# Analog.net
KiCad netlist of a schematic drawn in Altium Designer
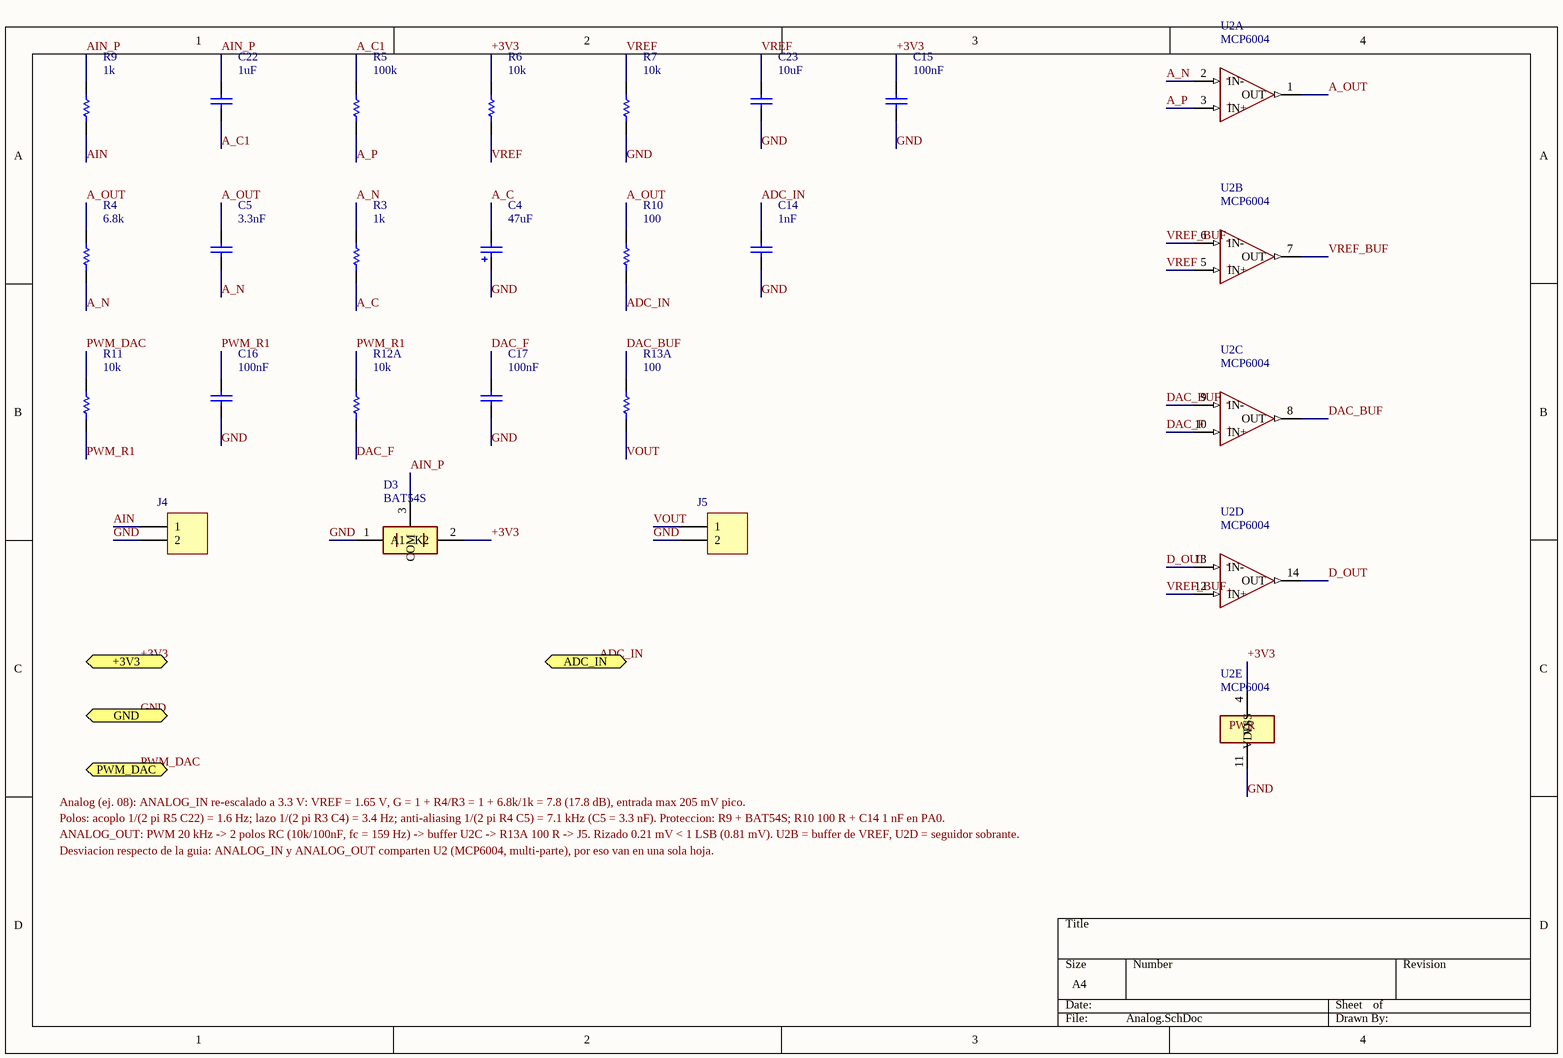
[diagram p0: Analog.SchDoc]

(export (version "E")
  (design (tool "Eeschema 10.0.6"))
  (components
    (comp (ref "C4")
      (value "47uF")
      (description "Electrolitico 47 uF 16 V (polo del lazo 3.4 Hz)")
      (fields
        (field (name "MANUFACTURER") "Panasonic")
        (field (name "MANUFACTURER PART NUMBER") "EEU-FR1C470")
        (field (name "PUBLISHER") "Altium Limited")
      )
      (libsource (lib "Miscellaneous Devices") (part "Cap Pol1"))
    )
    (comp (ref "C5")
      (value "3.3nF")
      (description "Capacitor 3.3nF")
      (fields
        (field (name "MANUFACTURER") "KEMET")
        (field (name "MANUFACTURER PART NUMBER") "C0603C3323.3nF")
        (field (name "PUBLISHER") "Altium Limited")
      )
      (libsource (lib "Miscellaneous Devices") (part "Cap"))
    )
    (comp (ref "C14")
      (value "1nF")
      (description "Capacitor 1nF")
      (fields
        (field (name "MANUFACTURER") "KEMET")
        (field (name "MANUFACTURER PART NUMBER") "C0603C1021nF")
        (field (name "PUBLISHER") "Altium Limited")
      )
      (libsource (lib "Miscellaneous Devices") (part "Cap"))
    )
    (comp (ref "C15")
      (value "100nF")
      (description "Capacitor 100nF")
      (fields
        (field (name "MANUFACTURER") "KEMET")
        (field (name "MANUFACTURER PART NUMBER") "C0603C100nF")
        (field (name "PUBLISHER") "Altium Limited")
      )
      (libsource (lib "Miscellaneous Devices") (part "Cap"))
    )
    (comp (ref "C16")
      (value "100nF")
      (description "Capacitor 100nF")
      (fields
        (field (name "MANUFACTURER") "KEMET")
        (field (name "MANUFACTURER PART NUMBER") "C0603C100nF")
        (field (name "PUBLISHER") "Altium Limited")
      )
      (libsource (lib "Miscellaneous Devices") (part "Cap"))
    )
    (comp (ref "C17")
      (value "100nF")
      (description "Capacitor 100nF")
      (fields
        (field (name "MANUFACTURER") "KEMET")
        (field (name "MANUFACTURER PART NUMBER") "C0603C100nF")
        (field (name "PUBLISHER") "Altium Limited")
      )
      (libsource (lib "Miscellaneous Devices") (part "Cap"))
    )
    (comp (ref "C22")
      (value "1uF")
      (description "Capacitor 1uF")
      (fields
        (field (name "MANUFACTURER") "KEMET")
        (field (name "MANUFACTURER PART NUMBER") "C0603C1051uF")
        (field (name "PUBLISHER") "Altium Limited")
      )
      (libsource (lib "Miscellaneous Devices") (part "Cap"))
    )
    (comp (ref "C23")
      (value "10uF")
      (description "Capacitor 10uF")
      (fields
        (field (name "MANUFACTURER") "KEMET")
        (field (name "MANUFACTURER PART NUMBER") "C0805C10610uF")
        (field (name "PUBLISHER") "Altium Limited")
      )
      (libsource (lib "Miscellaneous Devices") (part "Cap"))
    )
    (comp (ref "D3")
      (value "BAT54S")
      (footprint "SOT-23_N")
      (description "Dual Schottky series pair SOT-23 (clamp)")
      (fields (field (name "MANUFACTURER") "Nexperia"))
      (libsource (lib "*") (part "BAT54S"))
    )
    (comp (ref "J4")
      (value "Header 2")
      (description "Entrada analogica +-200 mV: pin1 senal, pin2 GND")
      (fields
        (field (name "MANUFACTURER") "Generic")
        (field (name "MANUFACTURER PART NUMBER") "Pin header 1x2")
        (field (name "PUBLISHER") "Altium Limited")
      )
      (libsource (lib "Miscellaneous Connectors") (part "Header 2"))
    )
    (comp (ref "J5")
      (value "Header 2")
      (description "Salida analogica 0-3.3 V: pin1 VOUT, pin2 GND")
      (fields
        (field (name "MANUFACTURER") "Generic")
        (field (name "MANUFACTURER PART NUMBER") "Pin header 1x2")
        (field (name "PUBLISHER") "Altium Limited")
      )
      (libsource (lib "Miscellaneous Connectors") (part "Header 2"))
    )
    (comp (ref "R3")
      (value "1k")
      (description "Resistor 1k 0603")
      (fields
        (field (name "MANUFACTURER") "Yageo")
        (field (name "MANUFACTURER PART NUMBER") "RC0603FR-071K")
        (field (name "PUBLISHER") "Altium Limited")
      )
      (libsource (lib "Miscellaneous Devices") (part "Res1"))
    )
    (comp (ref "R4")
      (value "6.8k")
      (description "Resistor 6.8k 0603")
      (fields
        (field (name "MANUFACTURER") "Yageo")
        (field (name "MANUFACTURER PART NUMBER") "RC0603FR-076.8K")
        (field (name "PUBLISHER") "Altium Limited")
      )
      (libsource (lib "Miscellaneous Devices") (part "Res1"))
    )
    (comp (ref "R5")
      (value "100k")
      (description "Resistor 100k 0603")
      (fields
        (field (name "MANUFACTURER") "Yageo")
        (field (name "MANUFACTURER PART NUMBER") "RC0603FR-07100K")
        (field (name "PUBLISHER") "Altium Limited")
      )
      (libsource (lib "Miscellaneous Devices") (part "Res1"))
    )
    (comp (ref "R6")
      (value "10k")
      (description "Resistor 10k 0603")
      (fields
        (field (name "MANUFACTURER") "Yageo")
        (field (name "MANUFACTURER PART NUMBER") "RC0603FR-0710K")
        (field (name "PUBLISHER") "Altium Limited")
      )
      (libsource (lib "Miscellaneous Devices") (part "Res1"))
    )
    (comp (ref "R7")
      (value "10k")
      (description "Resistor 10k 0603")
      (fields
        (field (name "MANUFACTURER") "Yageo")
        (field (name "MANUFACTURER PART NUMBER") "RC0603FR-0710K")
        (field (name "PUBLISHER") "Altium Limited")
      )
      (libsource (lib "Miscellaneous Devices") (part "Res1"))
    )
    (comp (ref "R9")
      (value "1k")
      (description "Resistor 1k 0603")
      (fields
        (field (name "MANUFACTURER") "Yageo")
        (field (name "MANUFACTURER PART NUMBER") "RC0603FR-071K")
        (field (name "PUBLISHER") "Altium Limited")
      )
      (libsource (lib "Miscellaneous Devices") (part "Res1"))
    )
    (comp (ref "R10")
      (value "100")
      (description "Resistor 100 0603")
      (fields
        (field (name "MANUFACTURER") "Yageo")
        (field (name "MANUFACTURER PART NUMBER") "RC0603FR-07100")
        (field (name "PUBLISHER") "Altium Limited")
      )
      (libsource (lib "Miscellaneous Devices") (part "Res1"))
    )
    (comp (ref "R11")
      (value "10k")
      (description "Resistor 10k 0603")
      (fields
        (field (name "MANUFACTURER") "Yageo")
        (field (name "MANUFACTURER PART NUMBER") "RC0603FR-0710K")
        (field (name "PUBLISHER") "Altium Limited")
      )
      (libsource (lib "Miscellaneous Devices") (part "Res1"))
    )
    (comp (ref "R12A")
      (value "10k")
      (description "Resistor 10k 0603")
      (fields
        (field (name "MANUFACTURER") "Yageo")
        (field (name "MANUFACTURER PART NUMBER") "RC0603FR-0710K")
        (field (name "PUBLISHER") "Altium Limited")
      )
      (libsource (lib "Miscellaneous Devices") (part "Res1"))
    )
    (comp (ref "R13A")
      (value "100")
      (description "Resistor 100 0603")
      (fields
        (field (name "MANUFACTURER") "Yageo")
        (field (name "MANUFACTURER PART NUMBER") "RC0603FR-07100")
        (field (name "PUBLISHER") "Altium Limited")
      )
      (libsource (lib "Miscellaneous Devices") (part "Res1"))
    )
    (comp (ref "U2")
      (value "MCP6004")
      (footprint "DIP-14")
      (description "MCP6004 quad op-amp rail-to-rail 1 MHz (A-D) + power part E, PDIP-14")
      (fields
        (field (name "MANUFACTURER") "Microchip")
        (field (name "MANUFACTURER PART NUMBER") "MCP6004-I/P")
      )
      (libsource (lib "*") (part "MCP6004"))
    )
  )
  (nets
    (net (code "1") (name "/+3V3") (class "Default")
      (node (ref "C15") (pin "2") (pinfunction "2_2") (pintype "passive"))
      (node (ref "D3") (pin "2") (pinfunction "K2_2") (pintype "passive"))
      (node (ref "R6") (pin "2") (pinfunction "2_2") (pintype "passive"))
      (node (ref "U2") (pin "4") (pinfunction "VDD_4") (pintype "power_in"))
    )
    (net (code "2") (name "/ADC_IN") (class "Default")
      (node (ref "C14") (pin "2") (pinfunction "2_2") (pintype "passive"))
      (node (ref "R10") (pin "1") (pinfunction "1_1") (pintype "passive"))
    )
    (net (code "3") (name "/AIN") (class "Default")
      (node (ref "J4") (pin "1") (pinfunction "1_1") (pintype "passive"))
      (node (ref "R9") (pin "1") (pinfunction "1_1") (pintype "passive"))
    )
    (net (code "4") (name "/AIN_P") (class "Default")
      (node (ref "C22") (pin "2") (pinfunction "2_2") (pintype "passive"))
      (node (ref "D3") (pin "3") (pinfunction "COM_3") (pintype "passive"))
      (node (ref "R9") (pin "2") (pinfunction "2_2") (pintype "passive"))
    )
    (net (code "5") (name "/A_C") (class "Default")
      (node (ref "C4") (pin "2") (pinfunction "2_2") (pintype "passive"))
      (node (ref "R3") (pin "1") (pinfunction "1_1") (pintype "passive"))
    )
    (net (code "6") (name "/A_C1") (class "Default")
      (node (ref "C22") (pin "1") (pinfunction "1_1") (pintype "passive"))
      (node (ref "R5") (pin "2") (pinfunction "2_2") (pintype "passive"))
    )
    (net (code "7") (name "/A_N") (class "Default")
      (node (ref "C5") (pin "1") (pinfunction "1_1") (pintype "passive"))
      (node (ref "R3") (pin "2") (pinfunction "2_2") (pintype "passive"))
      (node (ref "R4") (pin "1") (pinfunction "1_1") (pintype "passive"))
      (node (ref "U2") (pin "2") (pinfunction "IN-_2") (pintype "input"))
    )
    (net (code "8") (name "/A_OUT") (class "Default")
      (node (ref "C5") (pin "2") (pinfunction "2_2") (pintype "passive"))
      (node (ref "R10") (pin "2") (pinfunction "2_2") (pintype "passive"))
      (node (ref "R4") (pin "2") (pinfunction "2_2") (pintype "passive"))
      (node (ref "U2") (pin "1") (pinfunction "OUT_1") (pintype "output"))
    )
    (net (code "9") (name "/A_P") (class "Default")
      (node (ref "R5") (pin "1") (pinfunction "1_1") (pintype "passive"))
      (node (ref "U2") (pin "3") (pinfunction "IN+_3") (pintype "input"))
    )
    (net (code "10") (name "/DAC_BUF") (class "Default")
      (node (ref "R13A") (pin "2") (pinfunction "2_2") (pintype "passive"))
      (node (ref "U2") (pin "8") (pinfunction "OUT_8") (pintype "output"))
      (node (ref "U2") (pin "9") (pinfunction "IN-_9") (pintype "input"))
    )
    (net (code "11") (name "/DAC_F") (class "Default")
      (node (ref "C17") (pin "2") (pinfunction "2_2") (pintype "passive"))
      (node (ref "R12A") (pin "1") (pinfunction "1_1") (pintype "passive"))
      (node (ref "U2") (pin "10") (pinfunction "IN+_10") (pintype "input"))
    )
    (net (code "12") (name "/D_OUT") (class "Default")
      (node (ref "U2") (pin "13") (pinfunction "IN-_13") (pintype "input"))
      (node (ref "U2") (pin "14") (pinfunction "OUT_14") (pintype "output"))
    )
    (net (code "13") (name "/GND") (class "Default")
      (node (ref "C14") (pin "1") (pinfunction "1_1") (pintype "passive"))
      (node (ref "C15") (pin "1") (pinfunction "1_1") (pintype "passive"))
      (node (ref "C16") (pin "1") (pinfunction "1_1") (pintype "passive"))
      (node (ref "C17") (pin "1") (pinfunction "1_1") (pintype "passive"))
      (node (ref "C23") (pin "1") (pinfunction "1_1") (pintype "passive"))
      (node (ref "C4") (pin "1") (pinfunction "1_1") (pintype "passive"))
      (node (ref "D3") (pin "1") (pinfunction "A1_1") (pintype "passive"))
      (node (ref "J4") (pin "2") (pinfunction "2_2") (pintype "passive"))
      (node (ref "J5") (pin "2") (pinfunction "2_2") (pintype "passive"))
      (node (ref "R7") (pin "1") (pinfunction "1_1") (pintype "passive"))
      (node (ref "U2") (pin "11") (pinfunction "VSS_11") (pintype "power_in"))
    )
    (net (code "14") (name "/PWM_DAC") (class "Default")
      (node (ref "R11") (pin "2") (pinfunction "2_2") (pintype "passive"))
    )
    (net (code "15") (name "/PWM_R1") (class "Default")
      (node (ref "C16") (pin "2") (pinfunction "2_2") (pintype "passive"))
      (node (ref "R11") (pin "1") (pinfunction "1_1") (pintype "passive"))
      (node (ref "R12A") (pin "2") (pinfunction "2_2") (pintype "passive"))
    )
    (net (code "16") (name "/VOUT") (class "Default")
      (node (ref "J5") (pin "1") (pinfunction "1_1") (pintype "passive"))
      (node (ref "R13A") (pin "1") (pinfunction "1_1") (pintype "passive"))
    )
    (net (code "17") (name "/VREF") (class "Default")
      (node (ref "C23") (pin "2") (pinfunction "2_2") (pintype "passive"))
      (node (ref "R6") (pin "1") (pinfunction "1_1") (pintype "passive"))
      (node (ref "R7") (pin "2") (pinfunction "2_2") (pintype "passive"))
      (node (ref "U2") (pin "5") (pinfunction "IN+_5") (pintype "input"))
    )
    (net (code "18") (name "/VREF_BUF") (class "Default")
      (node (ref "U2") (pin "12") (pinfunction "IN+_12") (pintype "input"))
      (node (ref "U2") (pin "6") (pinfunction "IN-_6") (pintype "input"))
      (node (ref "U2") (pin "7") (pinfunction "OUT_7") (pintype "output"))
    )
  )
)
